# pCog100_Wifi_Sensor_TFT.net
KiCad netlist of a schematic drawn in EAGLE
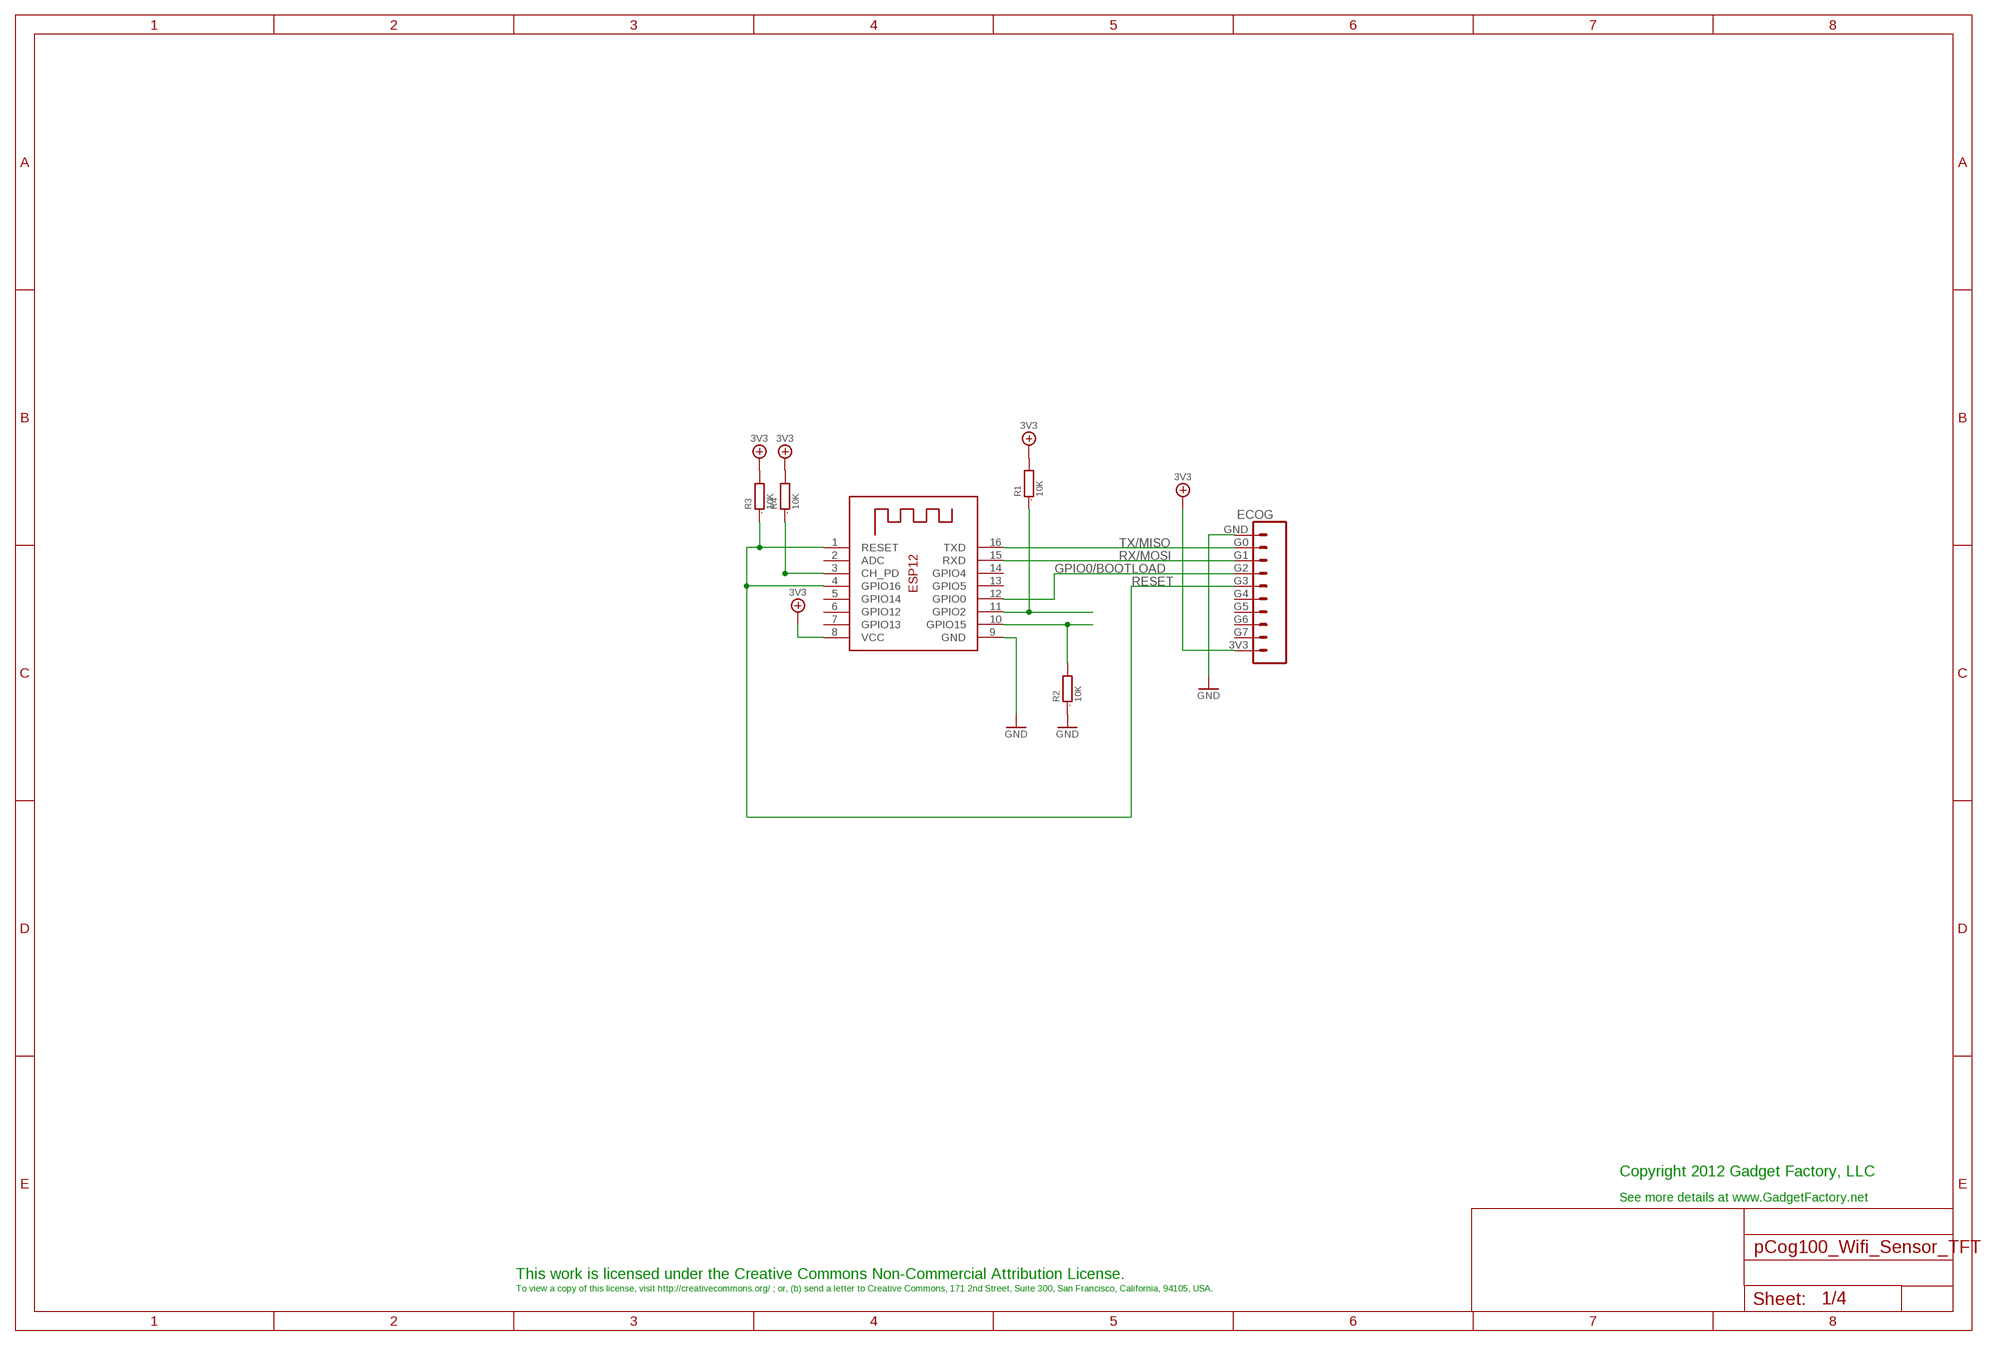
[diagram p0: schematic, sheet 1]
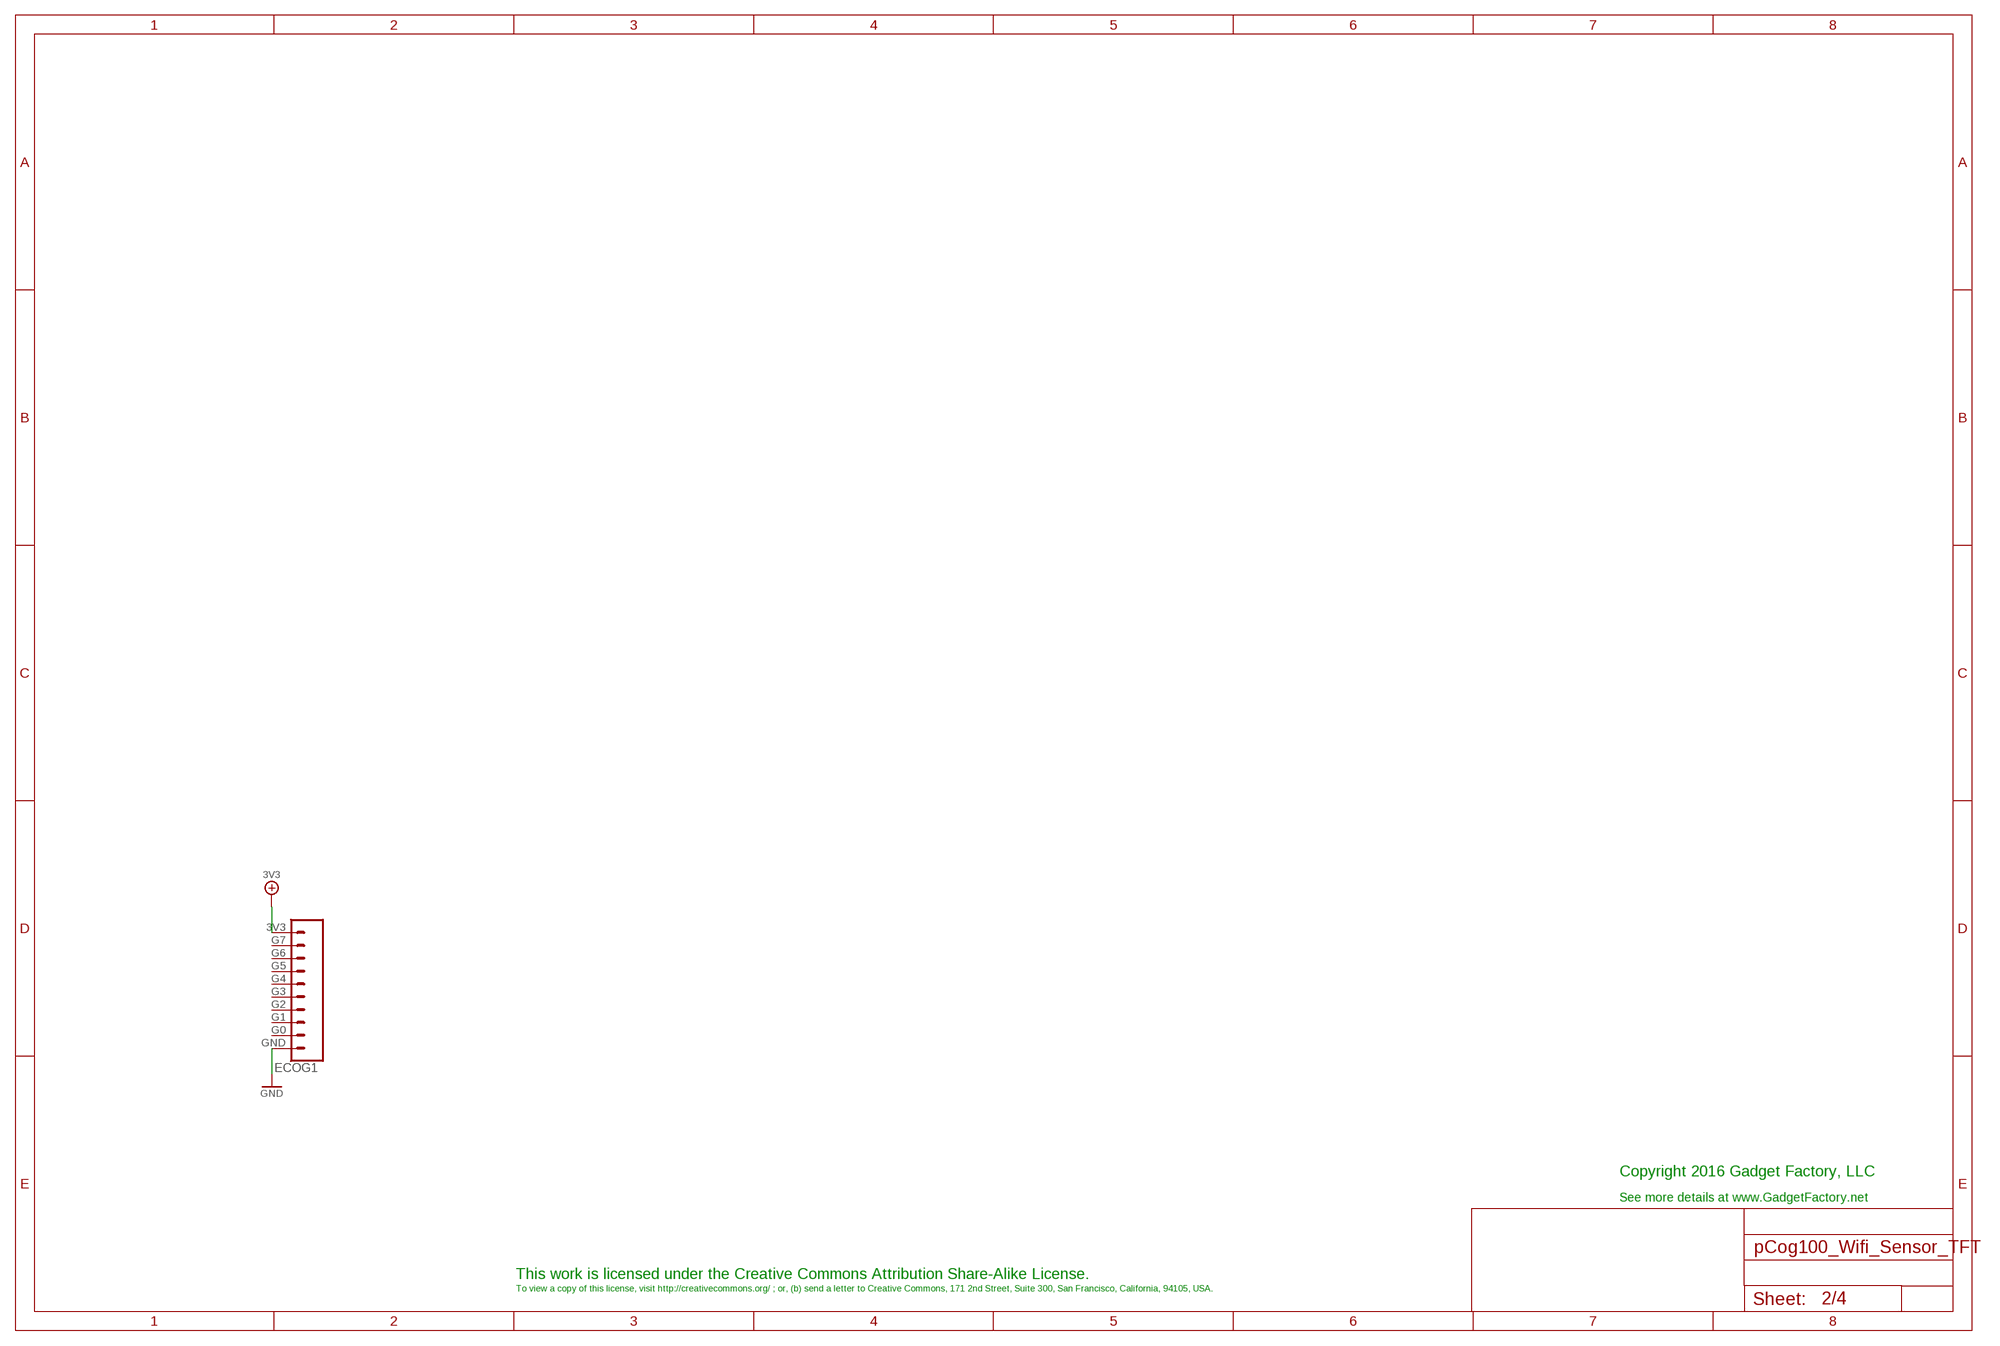
[diagram p1: schematic, sheet 2]
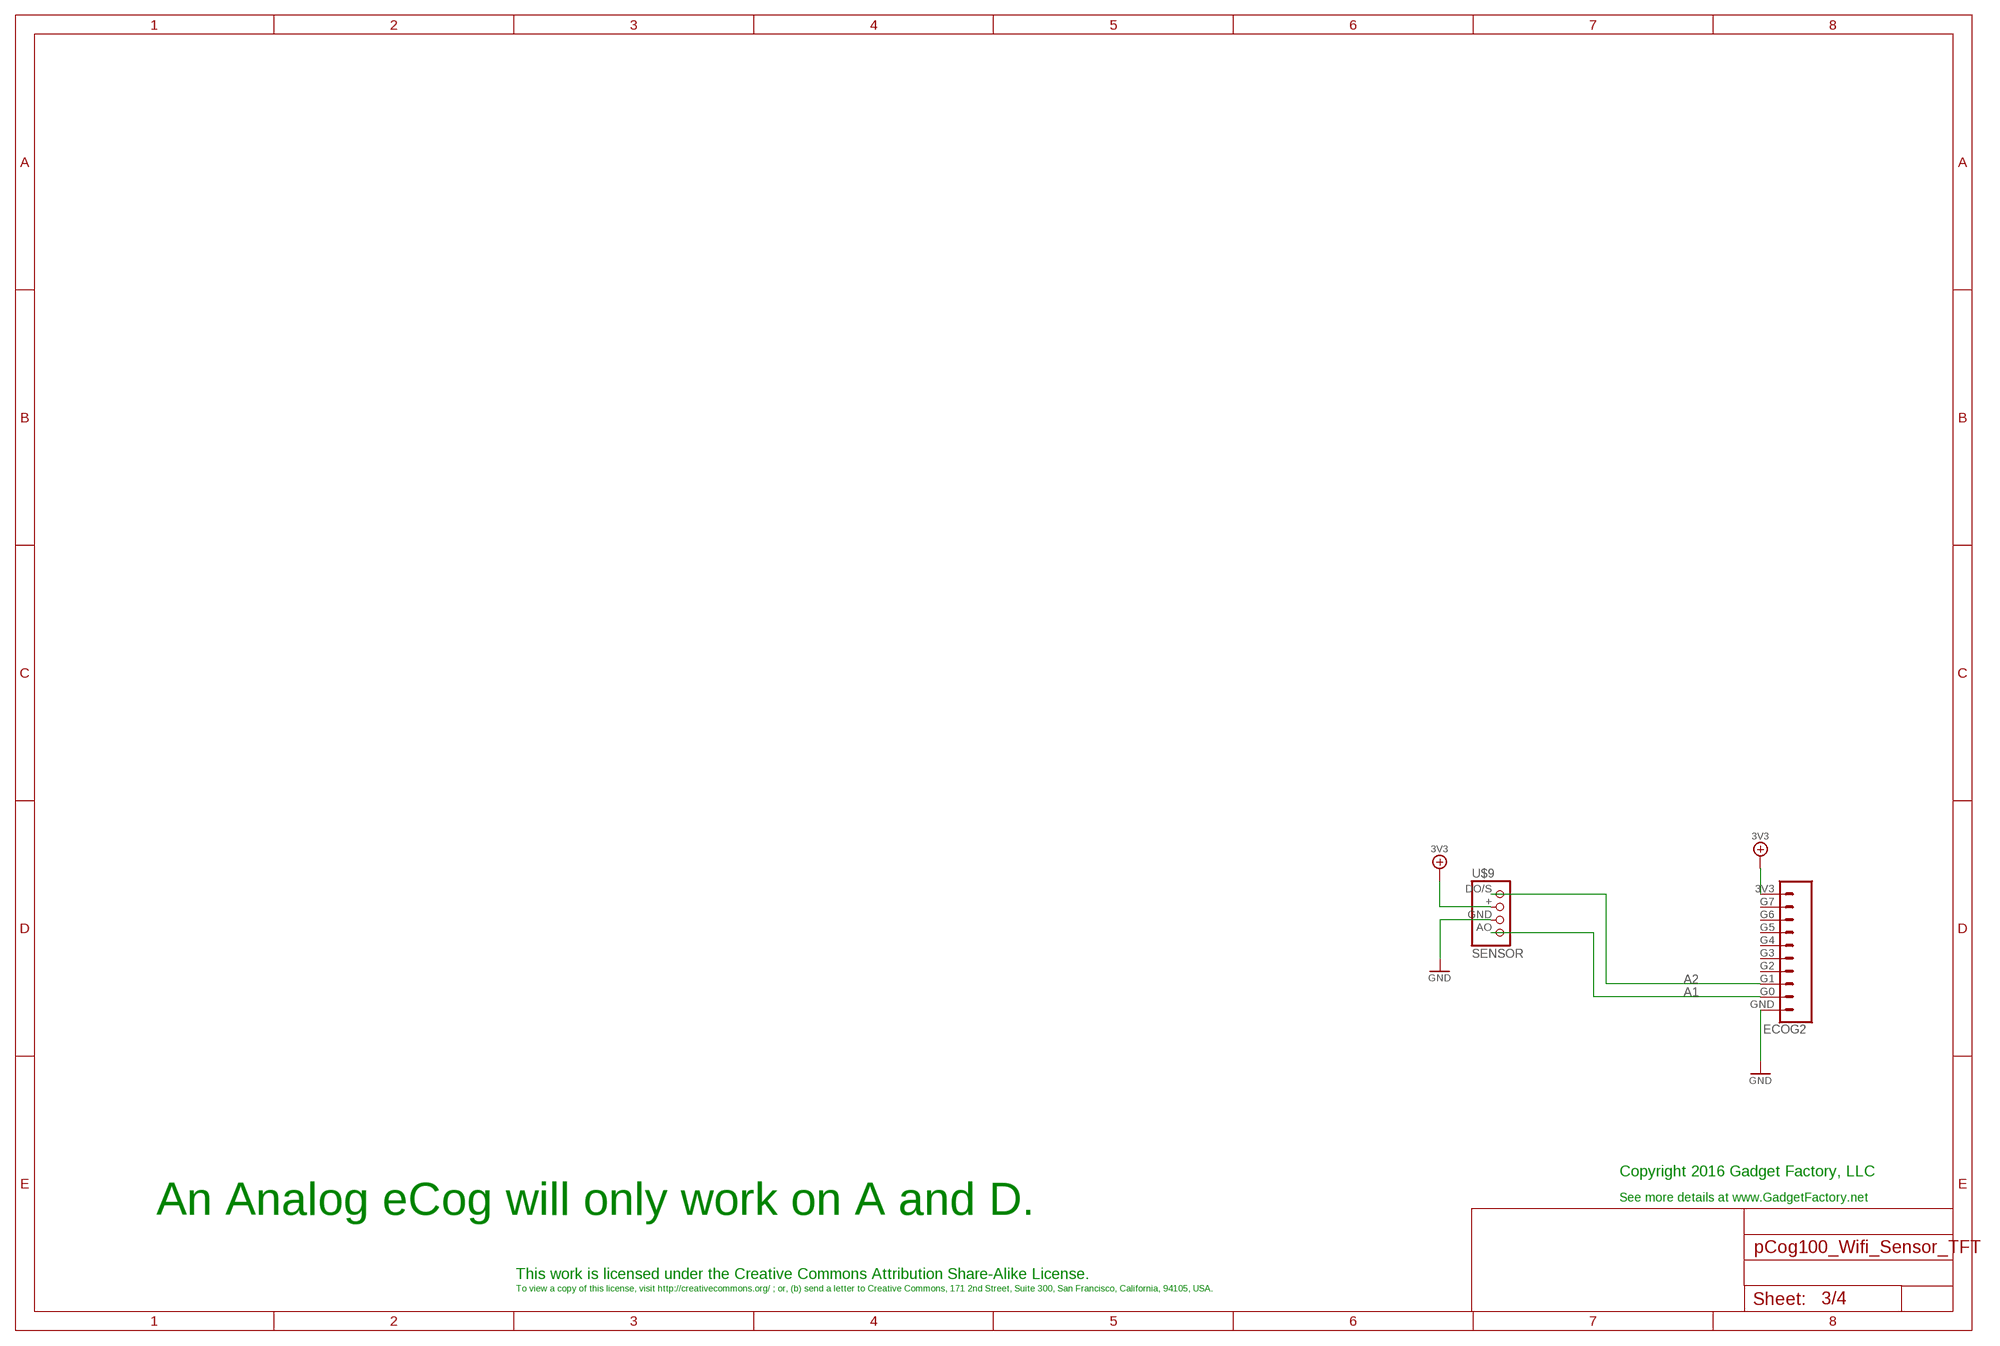
[diagram p2: schematic, sheet 3]
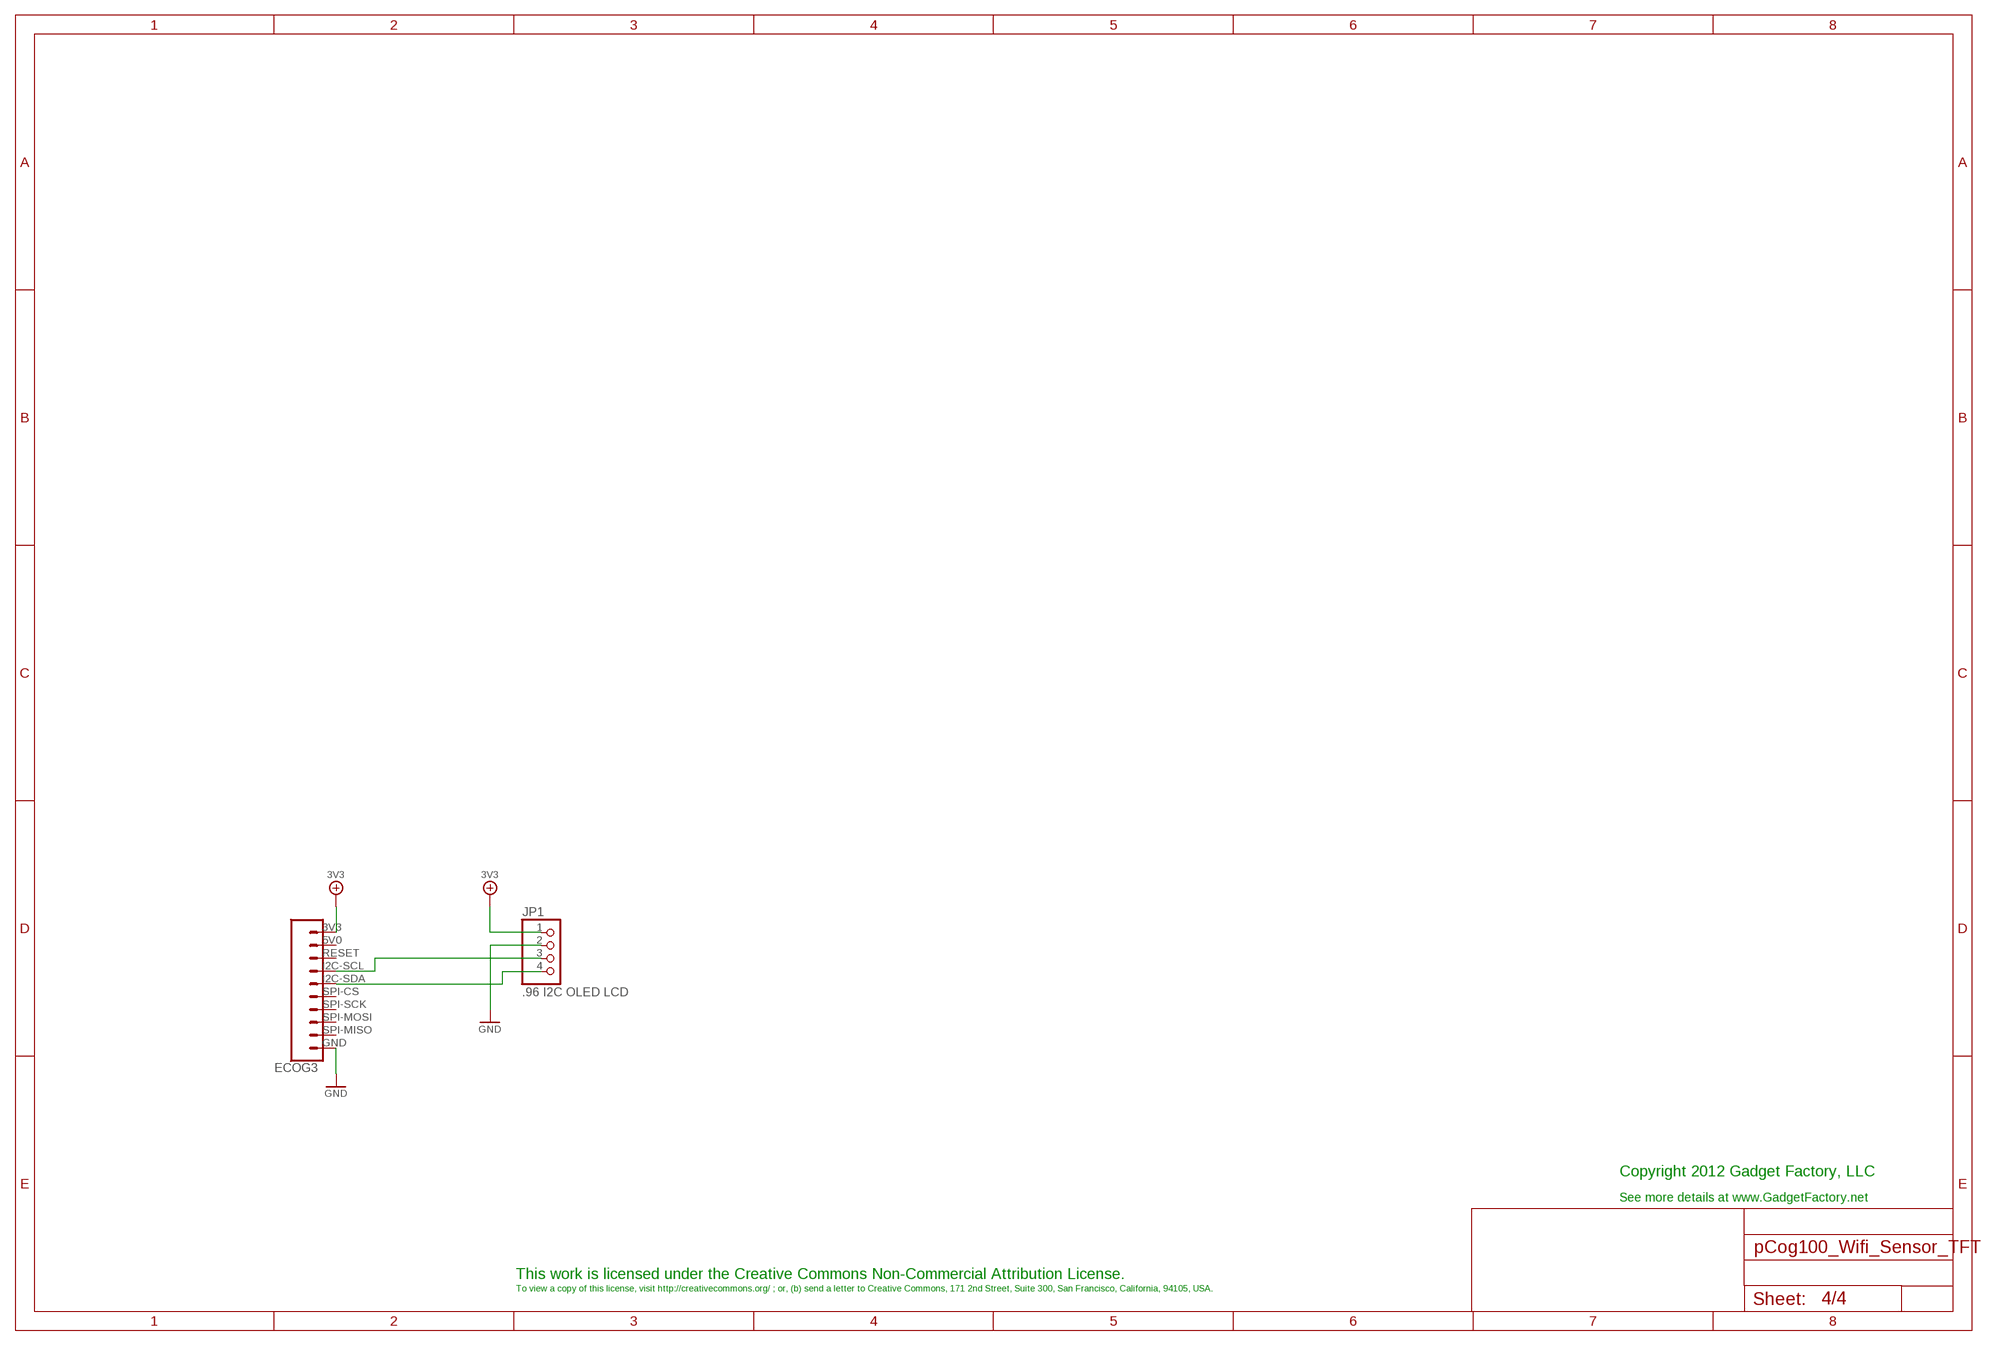
[diagram p3: schematic, sheet 4]

(export (version "E")
  (design (tool "Eeschema 10.0.6"))
  (components
    (comp (ref "ECOG2")
      (value "ECOG_GENERAL_ROWTHROUGHOLE")
      (footprint "eagle-import:ECOG_GENERAL_TH")
      (libsource (lib "eagle-import") (part "ECOG_GENERAL_ROWTHROUGHOLE"))
    )
    (comp (ref "U$9")
      (value "SENSOR")
      (footprint "eagle-import:SENSOR-HJX4")
      (libsource (lib "eagle-import") (part "SENSOR"))
    )
    (comp (ref "ECOG1")
      (value "ECOG_GENERAL_ROWSURFACEMOUNT")
      (footprint "eagle-import:ECOG_GENERAL_SMD")
      (libsource (lib "eagle-import") (part "ECOG_GENERAL_ROWSURFACEMOUNT"))
    )
    (comp (ref "ECOG")
      (value "ECOG_GENERAL_ROWTHROUGHOLE")
      (footprint "eagle-import:ECOG_GENERAL_TH")
      (libsource (lib "eagle-import") (part "ECOG_GENERAL_ROWTHROUGHOLE"))
    )
    (comp (ref "R1")
      (value "10K")
      (footprint "eagle-import:0805")
      (libsource (lib "eagle-import") (part "R0805"))
    )
    (comp (ref "R2")
      (value "10K")
      (footprint "eagle-import:0805")
      (libsource (lib "eagle-import") (part "R0805"))
    )
    (comp (ref "R3")
      (value "10K")
      (footprint "eagle-import:0805")
      (libsource (lib "eagle-import") (part "R0805"))
    )
    (comp (ref "R4")
      (value "10K")
      (footprint "eagle-import:0805")
      (libsource (lib "eagle-import") (part "R0805"))
    )
    (comp (ref "X1")
      (value "ESP-12")
      (footprint "eagle-import:ESP-12")
      (libsource (lib "eagle-import") (part "ESP-12"))
    )
    (comp (ref "ECOG3")
      (value "ECOG_BUSES_ROWTHROUGHHOLE")
      (footprint "eagle-import:ECOG_BUSES_TH")
      (libsource (lib "eagle-import") (part "ECOG_BUSES_ROWTHROUGHHOLE"))
    )
    (comp (ref "JP1")
      (value ".96 I2C OLED LCD")
      (footprint "eagle-import:1X04")
      (libsource (lib "eagle-import") (part "PINHD-1X4"))
    )
  )
  (nets
    (net (code "1") (name "3V3") (class "Default")
      (node (ref "ECOG") (pin "3V3") (pinfunction "3V3_3V3") (pintype "power_in"))
      (node (ref "ECOG1") (pin "3V3") (pinfunction "3V3_3V3") (pintype "power_in"))
      (node (ref "ECOG2") (pin "3V3") (pinfunction "3V3_3V3") (pintype "power_in"))
      (node (ref "ECOG3") (pin "3V3") (pinfunction "3V3_3V3") (pintype "passive"))
      (node (ref "JP1") (pin "1") (pinfunction "1_1") (pintype "passive"))
      (node (ref "R1") (pin "2") (pinfunction "2_2") (pintype "passive"))
      (node (ref "R3") (pin "2") (pinfunction "2_2") (pintype "passive"))
      (node (ref "R4") (pin "2") (pinfunction "2_2") (pintype "passive"))
      (node (ref "U$9") (pin "+") (pinfunction "+_+") (pintype "passive"))
      (node (ref "X1") (pin "8") (pinfunction "VCC_8") (pintype "power_in"))
    )
    (net (code "2") (name "A1") (class "Default")
      (node (ref "ECOG2") (pin "G0") (pinfunction "G0_G0") (pintype "passive"))
      (node (ref "U$9") (pin "AO") (pinfunction "AO_AO") (pintype "passive"))
    )
    (net (code "3") (name "A2") (class "Default")
      (node (ref "ECOG2") (pin "G1") (pinfunction "G1_G1") (pintype "passive"))
      (node (ref "U$9") (pin "DO/S") (pinfunction "DO/S_DO/S") (pintype "passive"))
    )
    (net (code "4") (name "GND") (class "Default")
      (node (ref "ECOG") (pin "GND") (pinfunction "GND_GND") (pintype "power_in"))
      (node (ref "ECOG1") (pin "GND") (pinfunction "GND_GND") (pintype "power_in"))
      (node (ref "ECOG2") (pin "GND") (pinfunction "GND_GND") (pintype "power_in"))
      (node (ref "ECOG3") (pin "GND") (pinfunction "GND_GND") (pintype "passive"))
      (node (ref "JP1") (pin "2") (pinfunction "2_2") (pintype "passive"))
      (node (ref "R2") (pin "1") (pinfunction "1_1") (pintype "passive"))
      (node (ref "U$9") (pin "GND") (pinfunction "GND_GND") (pintype "passive"))
      (node (ref "X1") (pin "9") (pinfunction "GND_9") (pintype "power_in"))
    )
    (net (code "5") (name "GPIO0{slash}BOOTLOAD") (class "Default")
      (node (ref "ECOG") (pin "G2") (pinfunction "G2_G2") (pintype "passive"))
      (node (ref "X1") (pin "12") (pinfunction "GPIO0_12") (pintype "bidirectional"))
    )
    (net (code "6") (name "Net-(ECOG3-PadI2C-SCL)") (class "Default")
      (node (ref "ECOG3") (pin "I2C-SCL") (pinfunction "I2C-SCL_I2C-SCL") (pintype "passive"))
      (node (ref "JP1") (pin "3") (pinfunction "3_3") (pintype "passive"))
    )
    (net (code "7") (name "Net-(ECOG3-PadI2C-SDA)") (class "Default")
      (node (ref "ECOG3") (pin "I2C-SDA") (pinfunction "I2C-SDA_I2C-SDA") (pintype "passive"))
      (node (ref "JP1") (pin "4") (pinfunction "4_4") (pintype "passive"))
    )
    (net (code "8") (name "Net-(X1-CH_PD)") (class "Default")
      (node (ref "R4") (pin "1") (pinfunction "1_1") (pintype "passive"))
      (node (ref "X1") (pin "3") (pinfunction "CH_PD_3") (pintype "input"))
    )
    (net (code "9") (name "Net-(X1-GPIO2)") (class "Default")
      (node (ref "R1") (pin "1") (pinfunction "1_1") (pintype "passive"))
      (node (ref "X1") (pin "11") (pinfunction "GPIO2_11") (pintype "bidirectional"))
    )
    (net (code "10") (name "Net-(X1-GPIO15)") (class "Default")
      (node (ref "R2") (pin "2") (pinfunction "2_2") (pintype "passive"))
      (node (ref "X1") (pin "10") (pinfunction "GPIO15_10") (pintype "bidirectional"))
    )
    (net (code "11") (name "RESET") (class "Default")
      (node (ref "ECOG") (pin "G3") (pinfunction "G3_G3") (pintype "passive"))
      (node (ref "R3") (pin "1") (pinfunction "1_1") (pintype "passive"))
      (node (ref "X1") (pin "1") (pinfunction "RESET_1") (pintype "input"))
      (node (ref "X1") (pin "4") (pinfunction "GPIO16_4") (pintype "bidirectional"))
    )
    (net (code "12") (name "RX{slash}MOSI") (class "Default")
      (node (ref "ECOG") (pin "G1") (pinfunction "G1_G1") (pintype "passive"))
      (node (ref "X1") (pin "15") (pinfunction "RXD_15") (pintype "input"))
    )
    (net (code "13") (name "TX{slash}MISO") (class "Default")
      (node (ref "ECOG") (pin "G0") (pinfunction "G0_G0") (pintype "passive"))
      (node (ref "X1") (pin "16") (pinfunction "TXD_16") (pintype "output"))
    )
    (net (code "14") (name "unconnected-(ECOG-PadG4)") (class "Default")
      (node (ref "ECOG") (pin "G4") (pinfunction "G4_G4") (pintype "passive"))
    )
    (net (code "15") (name "unconnected-(ECOG-PadG5)") (class "Default")
      (node (ref "ECOG") (pin "G5") (pinfunction "G5_G5") (pintype "passive"))
    )
    (net (code "16") (name "unconnected-(ECOG-PadG6)") (class "Default")
      (node (ref "ECOG") (pin "G6") (pinfunction "G6_G6") (pintype "passive"))
    )
    (net (code "17") (name "unconnected-(ECOG-PadG7)") (class "Default")
      (node (ref "ECOG") (pin "G7") (pinfunction "G7_G7") (pintype "passive"))
    )
    (net (code "18") (name "unconnected-(ECOG1-PadG0)") (class "Default")
      (node (ref "ECOG1") (pin "G0") (pinfunction "G0_G0") (pintype "passive"))
    )
    (net (code "19") (name "unconnected-(ECOG1-PadG1)") (class "Default")
      (node (ref "ECOG1") (pin "G1") (pinfunction "G1_G1") (pintype "passive"))
    )
    (net (code "20") (name "unconnected-(ECOG1-PadG2)") (class "Default")
      (node (ref "ECOG1") (pin "G2") (pinfunction "G2_G2") (pintype "passive"))
    )
    (net (code "21") (name "unconnected-(ECOG1-PadG3)") (class "Default")
      (node (ref "ECOG1") (pin "G3") (pinfunction "G3_G3") (pintype "passive"))
    )
    (net (code "22") (name "unconnected-(ECOG1-PadG4)") (class "Default")
      (node (ref "ECOG1") (pin "G4") (pinfunction "G4_G4") (pintype "passive"))
    )
    (net (code "23") (name "unconnected-(ECOG1-PadG5)") (class "Default")
      (node (ref "ECOG1") (pin "G5") (pinfunction "G5_G5") (pintype "passive"))
    )
    (net (code "24") (name "unconnected-(ECOG1-PadG6)") (class "Default")
      (node (ref "ECOG1") (pin "G6") (pinfunction "G6_G6") (pintype "passive"))
    )
    (net (code "25") (name "unconnected-(ECOG1-PadG7)") (class "Default")
      (node (ref "ECOG1") (pin "G7") (pinfunction "G7_G7") (pintype "passive"))
    )
    (net (code "26") (name "unconnected-(ECOG2-PadG2)") (class "Default")
      (node (ref "ECOG2") (pin "G2") (pinfunction "G2_G2") (pintype "passive"))
    )
    (net (code "27") (name "unconnected-(ECOG2-PadG3)") (class "Default")
      (node (ref "ECOG2") (pin "G3") (pinfunction "G3_G3") (pintype "passive"))
    )
    (net (code "28") (name "unconnected-(ECOG2-PadG4)") (class "Default")
      (node (ref "ECOG2") (pin "G4") (pinfunction "G4_G4") (pintype "passive"))
    )
    (net (code "29") (name "unconnected-(ECOG2-PadG5)") (class "Default")
      (node (ref "ECOG2") (pin "G5") (pinfunction "G5_G5") (pintype "passive"))
    )
    (net (code "30") (name "unconnected-(ECOG2-PadG6)") (class "Default")
      (node (ref "ECOG2") (pin "G6") (pinfunction "G6_G6") (pintype "passive"))
    )
    (net (code "31") (name "unconnected-(ECOG2-PadG7)") (class "Default")
      (node (ref "ECOG2") (pin "G7") (pinfunction "G7_G7") (pintype "passive"))
    )
    (net (code "32") (name "unconnected-(ECOG3-PadSPI-CS)") (class "Default")
      (node (ref "ECOG3") (pin "SPI-CS") (pinfunction "SPI-CS_SPI-CS") (pintype "passive"))
    )
    (net (code "33") (name "unconnected-(ECOG3-PadSPI-MISO)") (class "Default")
      (node (ref "ECOG3") (pin "SPI-MISO") (pinfunction "SPI-MISO_SPI-MISO") (pintype "passive"))
    )
    (net (code "34") (name "unconnected-(ECOG3-PadSPI-MOSI)") (class "Default")
      (node (ref "ECOG3") (pin "SPI-MOSI") (pinfunction "SPI-MOSI_SPI-MOSI") (pintype "passive"))
    )
    (net (code "35") (name "unconnected-(ECOG3-PadSPI-SCK)") (class "Default")
      (node (ref "ECOG3") (pin "SPI-SCK") (pinfunction "SPI-SCK_SPI-SCK") (pintype "passive"))
    )
    (net (code "36") (name "unconnected-(ECOG3-RSV-Pad5V0)") (class "Default")
      (node (ref "ECOG3") (pin "5V0") (pinfunction "RSV_5V0") (pintype "passive"))
    )
    (net (code "37") (name "unconnected-(ECOG3-RSV-PadRESET)") (class "Default")
      (node (ref "ECOG3") (pin "RESET") (pinfunction "RSV_RESET") (pintype "passive"))
    )
    (net (code "38") (name "unconnected-(X1-ADC-Pad2)") (class "Default")
      (node (ref "X1") (pin "2") (pinfunction "ADC_2") (pintype "passive"))
    )
    (net (code "39") (name "unconnected-(X1-GPIO4-Pad14)") (class "Default")
      (node (ref "X1") (pin "14") (pinfunction "GPIO4_14") (pintype "bidirectional"))
    )
    (net (code "40") (name "unconnected-(X1-GPIO5-Pad13)") (class "Default")
      (node (ref "X1") (pin "13") (pinfunction "GPIO5_13") (pintype "bidirectional"))
    )
    (net (code "41") (name "unconnected-(X1-GPIO12-Pad6)") (class "Default")
      (node (ref "X1") (pin "6") (pinfunction "GPIO12_6") (pintype "bidirectional"))
    )
    (net (code "42") (name "unconnected-(X1-GPIO13-Pad7)") (class "Default")
      (node (ref "X1") (pin "7") (pinfunction "GPIO13_7") (pintype "bidirectional"))
    )
    (net (code "43") (name "unconnected-(X1-GPIO14-Pad5)") (class "Default")
      (node (ref "X1") (pin "5") (pinfunction "GPIO14_5") (pintype "bidirectional"))
    )
  )
)
